# GZ7_1_x-CORE.net
KiCad netlist of a schematic drawn in Altium Designer
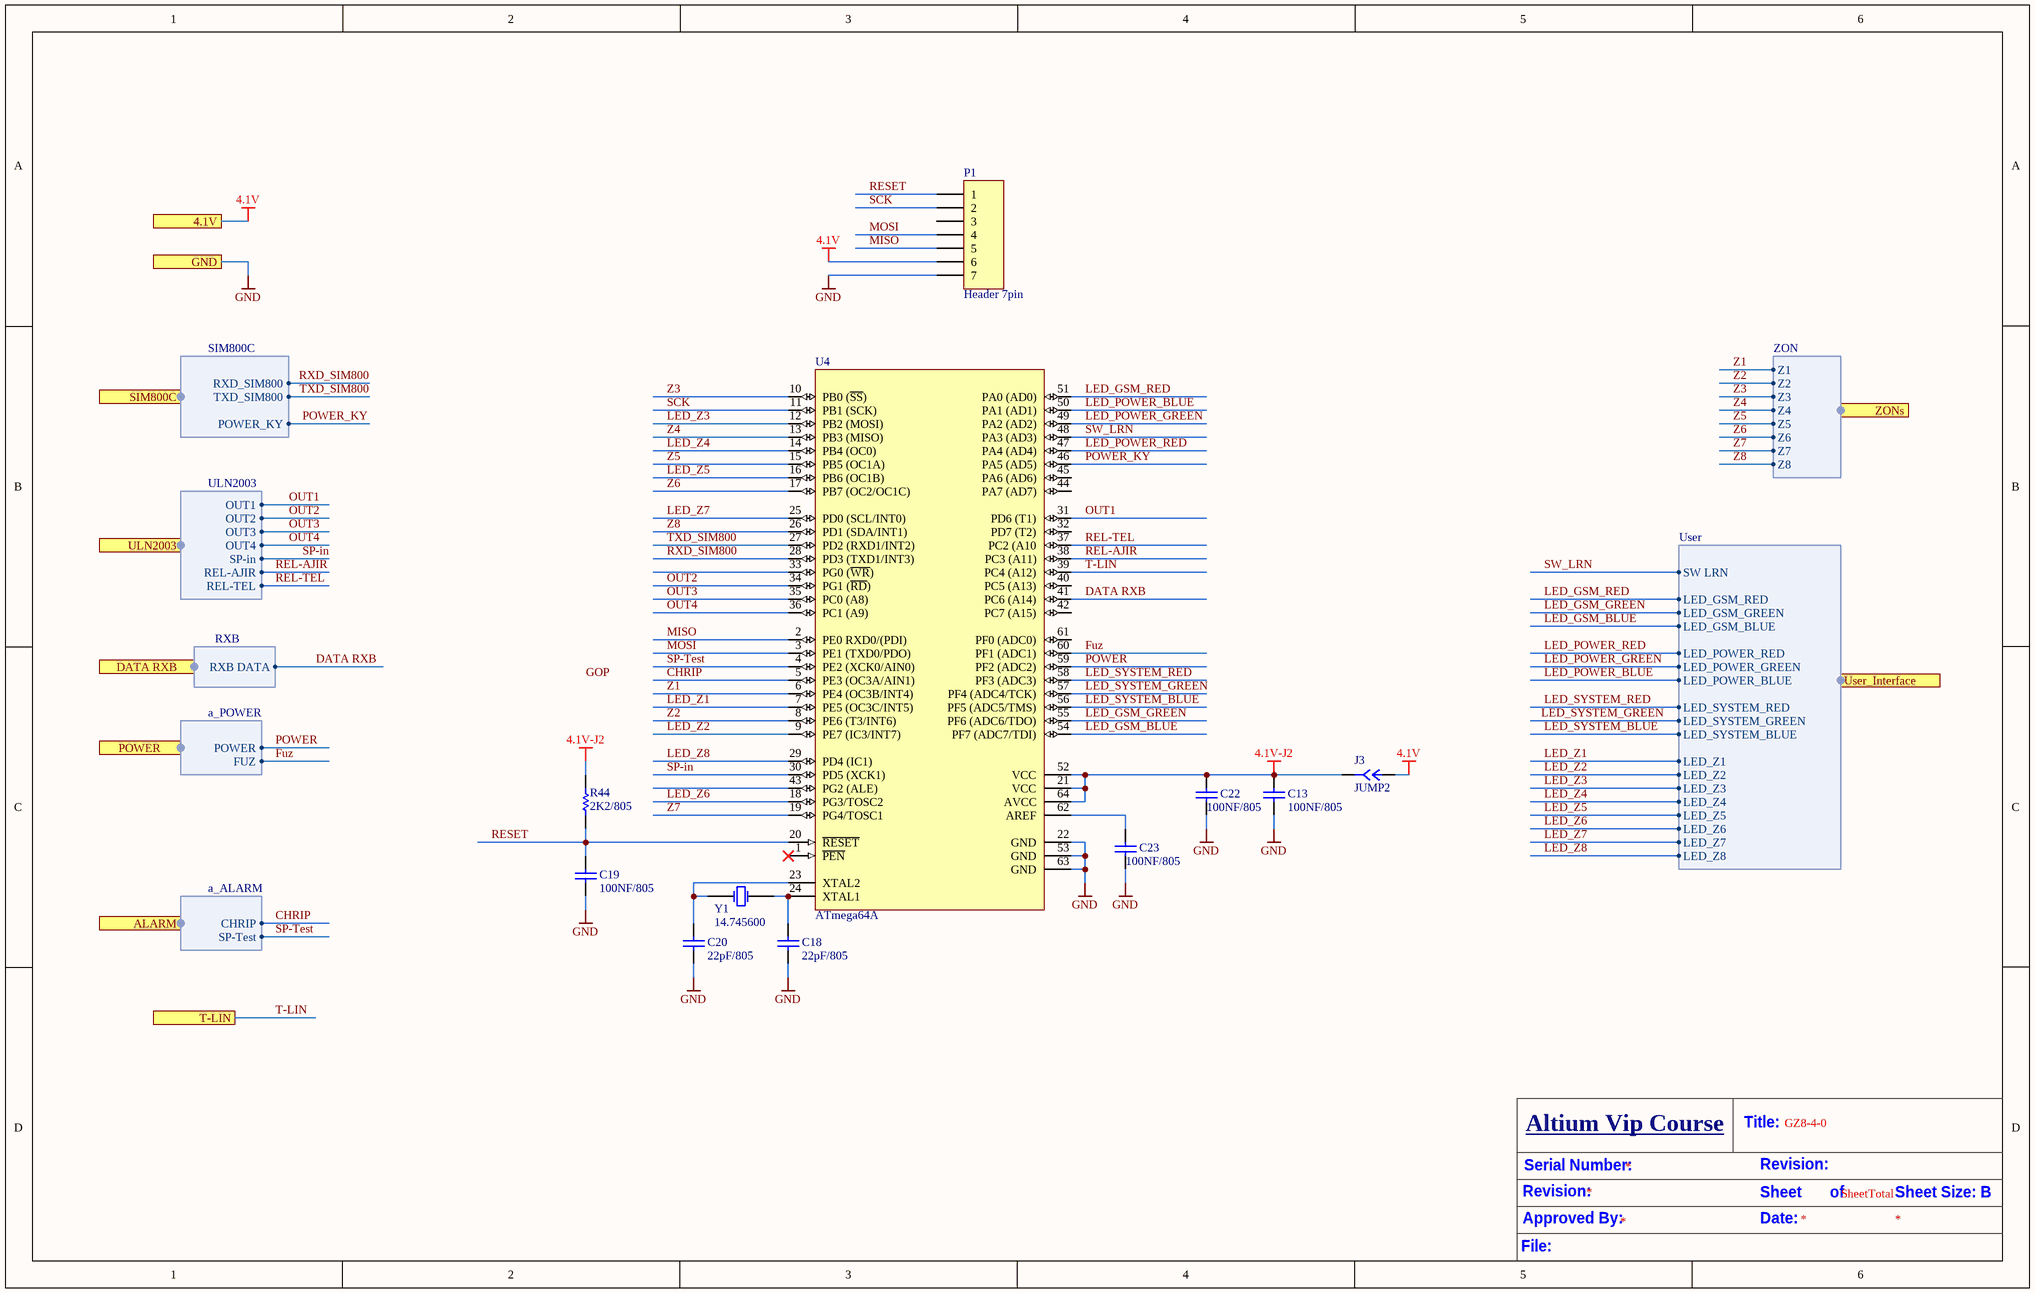
[diagram p0: GZ7_1_x-CORE.SchDoc]

(export (version "E")
  (design (tool "Eeschema 10.0.6"))
  (components
    (comp (ref "C13")
      (value "100NF/805")
      (footprint "MY805 COP")
      (description "CAP 0805")
      (fields (field (name "PUBLISHER") "Altium Limited"))
      (libsource (lib "Miscellaneous Devices") (part "Cap Semi"))
    )
    (comp (ref "C18")
      (value "22pF/805")
      (footprint "MY805 COP")
      (description "CAP 0805")
      (fields (field (name "PUBLISHER") "Altium Limited"))
      (libsource (lib "Miscellaneous Devices") (part "Cap Semi"))
    )
    (comp (ref "C19")
      (value "100NF/805")
      (footprint "MY805 COP")
      (description "CAP 0805")
      (fields (field (name "PUBLISHER") "Altium Limited"))
      (libsource (lib "Miscellaneous Devices") (part "Cap Semi"))
    )
    (comp (ref "C20")
      (value "22pF/805")
      (footprint "MY805 COP")
      (description "CAP 0805")
      (fields (field (name "PUBLISHER") "Altium Limited"))
      (libsource (lib "Miscellaneous Devices") (part "Cap Semi"))
    )
    (comp (ref "C22")
      (value "100NF/805")
      (footprint "MY805 COP")
      (description "CAP 0805")
      (fields (field (name "PUBLISHER") "Altium Limited"))
      (libsource (lib "Miscellaneous Devices") (part "Cap Semi"))
    )
    (comp (ref "C23")
      (value "100NF/805")
      (footprint "MY805 COP")
      (description "CAP 0805")
      (fields (field (name "PUBLISHER") "Altium Limited"))
      (libsource (lib "Miscellaneous Devices") (part "Cap Semi"))
    )
    (comp (ref "J3") (value "JUMP2") (footprint "JUMP3") (libsource (lib "Ebrahim") (part "JUMP2")))
    (comp (ref "P1")
      (value "Header 7pin")
      (footprint "HDR_P_GZ4")
      (description "Header, 7-Pin")
      (fields (field (name "PUBLISHER") "Altium Limited"))
      (libsource (lib "Miscellaneous Connectors") (part "Header 7"))
    )
    (comp (ref "R44")
      (value "2K2/805")
      (footprint "my805")
      (description "RES 805")
      (fields (field (name "PUBLISHER") "Altium Limited"))
      (libsource (lib "Miscellaneous Devices") (part "Res1"))
    )
    (comp (ref "U4")
      (value "ATmega64A")
      (footprint "TQFP64_GZ4E_1")
      (description "8-Bit AVR Microcontroller")
      (fields (field (name "PUBLISHER") "Altium Limited"))
      (libsource (lib "Atmel Microcontroller 8-Bit AVR") (part "ATmega64-16AC"))
    )
    (comp (ref "Y1")
      (value "14.745600")
      (footprint "Crystal SMD")
      (description "Crystal Oscillator")
      (fields (field (name "PUBLISHER") "Altium Limited"))
      (libsource (lib "Miscellaneous Devices") (part "XTAL"))
    )
  )
  (nets
    (net (code "8") (name "/CHRIP") (class "Default")
      (node (ref "U4") (pin "5") (pinfunction "PE3_(OC3A/AIN1)_5") (pintype "bidirectional"))
    )
    (net (code "9") (name "/DATA RXB") (class "Default")
      (node (ref "U4") (pin "41") (pinfunction "PC6_(A14)_41") (pintype "bidirectional"))
    )
    (net (code "10") (name "/Fuz") (class "Default")
      (node (ref "U4") (pin "60") (pinfunction "PF1_(ADC1)_60") (pintype "bidirectional"))
    )
    (net (code "12") (name "/LED_GSM_BLUE") (class "Default")
      (node (ref "U4") (pin "54") (pinfunction "PF7_(ADC7/TDI)_54") (pintype "bidirectional"))
    )
    (net (code "13") (name "/LED_GSM_GREEN") (class "Default")
      (node (ref "U4") (pin "55") (pinfunction "PF6_(ADC6/TDO)_55") (pintype "bidirectional"))
    )
    (net (code "14") (name "/LED_GSM_RED") (class "Default")
      (node (ref "U4") (pin "51") (pinfunction "PA0_(AD0)_51") (pintype "bidirectional"))
    )
    (net (code "15") (name "/LED_POWER_BLUE") (class "Default")
      (node (ref "U4") (pin "50") (pinfunction "PA1_(AD1)_50") (pintype "bidirectional"))
    )
    (net (code "16") (name "/LED_POWER_GREEN") (class "Default")
      (node (ref "U4") (pin "49") (pinfunction "PA2_(AD2)_49") (pintype "bidirectional"))
    )
    (net (code "17") (name "/LED_POWER_RED") (class "Default")
      (node (ref "U4") (pin "47") (pinfunction "PA4_(AD4)_47") (pintype "bidirectional"))
    )
    (net (code "18") (name "/LED_SYSTEM_BLUE") (class "Default")
      (node (ref "U4") (pin "56") (pinfunction "PF5_(ADC5/TMS)_56") (pintype "bidirectional"))
    )
    (net (code "19") (name "/LED_SYSTEM_GREEN") (class "Default")
      (node (ref "U4") (pin "57") (pinfunction "PF4_(ADC4/TCK)_57") (pintype "bidirectional"))
    )
    (net (code "20") (name "/LED_SYSTEM_RED") (class "Default")
      (node (ref "U4") (pin "58") (pinfunction "PF3_(ADC3)_58") (pintype "bidirectional"))
    )
    (net (code "21") (name "/LED_Z1") (class "Default")
      (node (ref "U4") (pin "7") (pinfunction "PE5_(OC3C/INT5)_7") (pintype "bidirectional"))
    )
    (net (code "22") (name "/LED_Z2") (class "Default")
      (node (ref "U4") (pin "9") (pinfunction "PE7_(IC3/INT7)_9") (pintype "bidirectional"))
    )
    (net (code "23") (name "/LED_Z3") (class "Default")
      (node (ref "U4") (pin "12") (pinfunction "PB2_(MOSI)_12") (pintype "bidirectional"))
    )
    (net (code "24") (name "/LED_Z4") (class "Default")
      (node (ref "U4") (pin "14") (pinfunction "PB4_(OC0)_14") (pintype "bidirectional"))
    )
    (net (code "25") (name "/LED_Z5") (class "Default")
      (node (ref "U4") (pin "16") (pinfunction "PB6_(OC1B)_16") (pintype "bidirectional"))
    )
    (net (code "26") (name "/LED_Z6") (class "Default")
      (node (ref "U4") (pin "18") (pinfunction "PG3/TOSC2_18") (pintype "bidirectional"))
    )
    (net (code "27") (name "/LED_Z7") (class "Default")
      (node (ref "U4") (pin "25") (pinfunction "PD0_(SCL/INT0)_25") (pintype "bidirectional"))
    )
    (net (code "28") (name "/LED_Z8") (class "Default")
      (node (ref "U4") (pin "29") (pinfunction "PD4_(IC1)_29") (pintype "bidirectional"))
    )
    (net (code "29") (name "/MISO") (class "Default")
      (node (ref "P1") (pin "5") (pinfunction "5_5") (pintype "passive"))
      (node (ref "U4") (pin "2") (pinfunction "PE0_RXD0/(PDI)_2") (pintype "bidirectional"))
    )
    (net (code "30") (name "/MOSI") (class "Default")
      (node (ref "P1") (pin "4") (pinfunction "4_4") (pintype "passive"))
      (node (ref "U4") (pin "3") (pinfunction "PE1_(TXD0/PDO)_3") (pintype "bidirectional"))
    )
    (net (code "31") (name "/OUT1") (class "Default")
      (node (ref "U4") (pin "31") (pinfunction "PD6_(T1)_31") (pintype "bidirectional"))
    )
    (net (code "32") (name "/OUT2") (class "Default")
      (node (ref "U4") (pin "34") (pinfunction "PG1_(~{RD})_34") (pintype "bidirectional"))
    )
    (net (code "33") (name "/OUT3") (class "Default")
      (node (ref "U4") (pin "35") (pinfunction "PC0_(A8)_35") (pintype "bidirectional"))
    )
    (net (code "34") (name "/OUT4") (class "Default")
      (node (ref "U4") (pin "36") (pinfunction "PC1_(A9)_36") (pintype "bidirectional"))
    )
    (net (code "35") (name "/POWER") (class "Default")
      (node (ref "U4") (pin "59") (pinfunction "PF2_(ADC2)_59") (pintype "bidirectional"))
    )
    (net (code "36") (name "/POWER_KY") (class "Default")
      (node (ref "U4") (pin "46") (pinfunction "PA5_(AD5)_46") (pintype "bidirectional"))
    )
    (net (code "37") (name "/REL-AJIR") (class "Default")
      (node (ref "U4") (pin "38") (pinfunction "PC3_(A11)_38") (pintype "bidirectional"))
    )
    (net (code "38") (name "/REL-TEL") (class "Default")
      (node (ref "U4") (pin "37") (pinfunction "PC2_(A10_37") (pintype "bidirectional"))
    )
    (net (code "39") (name "/RESET") (class "Default")
      (node (ref "C19") (pin "1") (pinfunction "1_1") (pintype "passive"))
      (node (ref "P1") (pin "1") (pinfunction "1_1") (pintype "passive"))
      (node (ref "R44") (pin "2") (pinfunction "2_2") (pintype "passive"))
      (node (ref "U4") (pin "20") (pinfunction "~{RESET}_20") (pintype "input"))
    )
    (net (code "40") (name "/RXD_SIM800") (class "Default")
      (node (ref "U4") (pin "28") (pinfunction "PD3_(TXD1/INT3)_28") (pintype "bidirectional"))
    )
    (net (code "41") (name "/SCK") (class "Default")
      (node (ref "P1") (pin "2") (pinfunction "2_2") (pintype "passive"))
      (node (ref "U4") (pin "11") (pinfunction "PB1_(SCK)_11") (pintype "bidirectional"))
    )
    (net (code "42") (name "/SP-Test") (class "Default")
      (node (ref "U4") (pin "4") (pinfunction "PE2_(XCK0/AIN0)_4") (pintype "bidirectional"))
    )
    (net (code "43") (name "/SP-in") (class "Default")
      (node (ref "U4") (pin "30") (pinfunction "PD5_(XCK1)_30") (pintype "bidirectional"))
    )
    (net (code "44") (name "/SW_LRN") (class "Default")
      (node (ref "U4") (pin "48") (pinfunction "PA3_(AD3)_48") (pintype "bidirectional"))
    )
    (net (code "45") (name "/T-LIN") (class "Default")
      (node (ref "U4") (pin "39") (pinfunction "PC4_(A12)_39") (pintype "bidirectional"))
    )
    (net (code "46") (name "/TXD_SIM800") (class "Default")
      (node (ref "U4") (pin "27") (pinfunction "PD2_(RXD1/INT2)_27") (pintype "bidirectional"))
    )
    (net (code "47") (name "/Z1") (class "Default")
      (node (ref "U4") (pin "6") (pinfunction "PE4_(OC3B/INT4)_6") (pintype "bidirectional"))
    )
    (net (code "48") (name "/Z2") (class "Default")
      (node (ref "U4") (pin "8") (pinfunction "PE6_(T3/INT6)_8") (pintype "bidirectional"))
    )
    (net (code "49") (name "/Z3") (class "Default")
      (node (ref "U4") (pin "10") (pinfunction "PB0_(~{SS})_10") (pintype "bidirectional"))
    )
    (net (code "50") (name "/Z4") (class "Default")
      (node (ref "U4") (pin "13") (pinfunction "PB3_(MISO)_13") (pintype "bidirectional"))
    )
    (net (code "51") (name "/Z5") (class "Default")
      (node (ref "U4") (pin "15") (pinfunction "PB5_(OC1A)_15") (pintype "bidirectional"))
    )
    (net (code "52") (name "/Z6") (class "Default")
      (node (ref "U4") (pin "17") (pinfunction "PB7_(OC2/OC1C)_17") (pintype "bidirectional"))
    )
    (net (code "53") (name "/Z7") (class "Default")
      (node (ref "U4") (pin "19") (pinfunction "PG4/TOSC1_19") (pintype "bidirectional"))
    )
    (net (code "54") (name "/Z8") (class "Default")
      (node (ref "U4") (pin "26") (pinfunction "PD1_(SDA/INT1)_26") (pintype "bidirectional"))
    )
    (net (code "62") (name "4.1V") (class "Default")
      (node (ref "J3") (pin "2") (pinfunction "2_2") (pintype "passive"))
      (node (ref "P1") (pin "6") (pinfunction "6_6") (pintype "passive"))
    )
    (net (code "63") (name "4.1V-J2") (class "Default")
      (node (ref "C13") (pin "1") (pinfunction "1_1") (pintype "passive"))
      (node (ref "C22") (pin "1") (pinfunction "1_1") (pintype "passive"))
      (node (ref "J3") (pin "1") (pinfunction "1_1") (pintype "passive"))
      (node (ref "R44") (pin "1") (pinfunction "1_1") (pintype "passive"))
      (node (ref "U4") (pin "21") (pinfunction "VCC_21") (pintype "power_in"))
      (node (ref "U4") (pin "52") (pinfunction "VCC_52") (pintype "power_in"))
      (node (ref "U4") (pin "64") (pinfunction "AVCC_64") (pintype "power_in"))
    )
    (net (code "64") (name "GND") (class "Default")
      (node (ref "C13") (pin "2") (pinfunction "2_2") (pintype "passive"))
      (node (ref "C18") (pin "2") (pinfunction "2_2") (pintype "passive"))
      (node (ref "C19") (pin "2") (pinfunction "2_2") (pintype "passive"))
      (node (ref "C20") (pin "2") (pinfunction "2_2") (pintype "passive"))
      (node (ref "C22") (pin "2") (pinfunction "2_2") (pintype "passive"))
      (node (ref "C23") (pin "2") (pinfunction "2_2") (pintype "passive"))
      (node (ref "P1") (pin "7") (pinfunction "7_7") (pintype "passive"))
      (node (ref "U4") (pin "22") (pinfunction "GND_22") (pintype "power_in"))
      (node (ref "U4") (pin "53") (pinfunction "GND_53") (pintype "power_in"))
      (node (ref "U4") (pin "63") (pinfunction "GND_63") (pintype "power_in"))
    )
    (net (code "65") (name "Net-(U4-AREF)") (class "Default")
      (node (ref "C23") (pin "1") (pinfunction "1_1") (pintype "passive"))
      (node (ref "U4") (pin "62") (pinfunction "AREF_62") (pintype "passive"))
    )
    (net (code "66") (name "Net-(U4-XTAL1)") (class "Default")
      (node (ref "C18") (pin "1") (pinfunction "1_1") (pintype "passive"))
      (node (ref "U4") (pin "24") (pinfunction "XTAL1_24") (pintype "passive"))
      (node (ref "Y1") (pin "2") (pinfunction "OSC2_2") (pintype "passive"))
    )
    (net (code "67") (name "Net-(U4-XTAL2)") (class "Default")
      (node (ref "C20") (pin "1") (pinfunction "1_1") (pintype "passive"))
      (node (ref "U4") (pin "23") (pinfunction "XTAL2_23") (pintype "passive"))
      (node (ref "Y1") (pin "1") (pinfunction "OSC1_1") (pintype "passive"))
    )
    (net (code "68") (name "unconnected-(P1-Pad3)") (class "Default")
      (node (ref "P1") (pin "3") (pinfunction "3_3") (pintype "passive"))
    )
    (net (code "69") (name "unconnected-(U4-PA6_(AD6)-Pad45)") (class "Default")
      (node (ref "U4") (pin "45") (pinfunction "PA6_(AD6)_45") (pintype "bidirectional"))
    )
    (net (code "70") (name "unconnected-(U4-PA7_(AD7)-Pad44)") (class "Default")
      (node (ref "U4") (pin "44") (pinfunction "PA7_(AD7)_44") (pintype "bidirectional"))
    )
    (net (code "71") (name "unconnected-(U4-PC5_(A13)-Pad40)") (class "Default")
      (node (ref "U4") (pin "40") (pinfunction "PC5_(A13)_40") (pintype "bidirectional"))
    )
    (net (code "72") (name "unconnected-(U4-PC7_(A15)-Pad42)") (class "Default")
      (node (ref "U4") (pin "42") (pinfunction "PC7_(A15)_42") (pintype "bidirectional"))
    )
    (net (code "73") (name "unconnected-(U4-PD7_(T2)-Pad32)") (class "Default")
      (node (ref "U4") (pin "32") (pinfunction "PD7_(T2)_32") (pintype "bidirectional"))
    )
    (net (code "74") (name "unconnected-(U4-PF0_(ADC0)-Pad61)") (class "Default")
      (node (ref "U4") (pin "61") (pinfunction "PF0_(ADC0)_61") (pintype "bidirectional"))
    )
    (net (code "75") (name "unconnected-(U4-PG0_(~{WR})-Pad33)") (class "Default")
      (node (ref "U4") (pin "33") (pinfunction "PG0_(~{WR})_33") (pintype "bidirectional"))
    )
    (net (code "76") (name "unconnected-(U4-PG2_(ALE)-Pad43)") (class "Default")
      (node (ref "U4") (pin "43") (pinfunction "PG2_(ALE)_43") (pintype "bidirectional"))
    )
    (net (code "77") (name "unconnected-(U4-~{PEN}-Pad1)") (class "Default")
      (node (ref "U4") (pin "1") (pinfunction "~{PEN}_1") (pintype "input+no_connect"))
    )
  )
)
